# pizero-boardtest.net
KiCad netlist of a schematic drawn in EAGLE
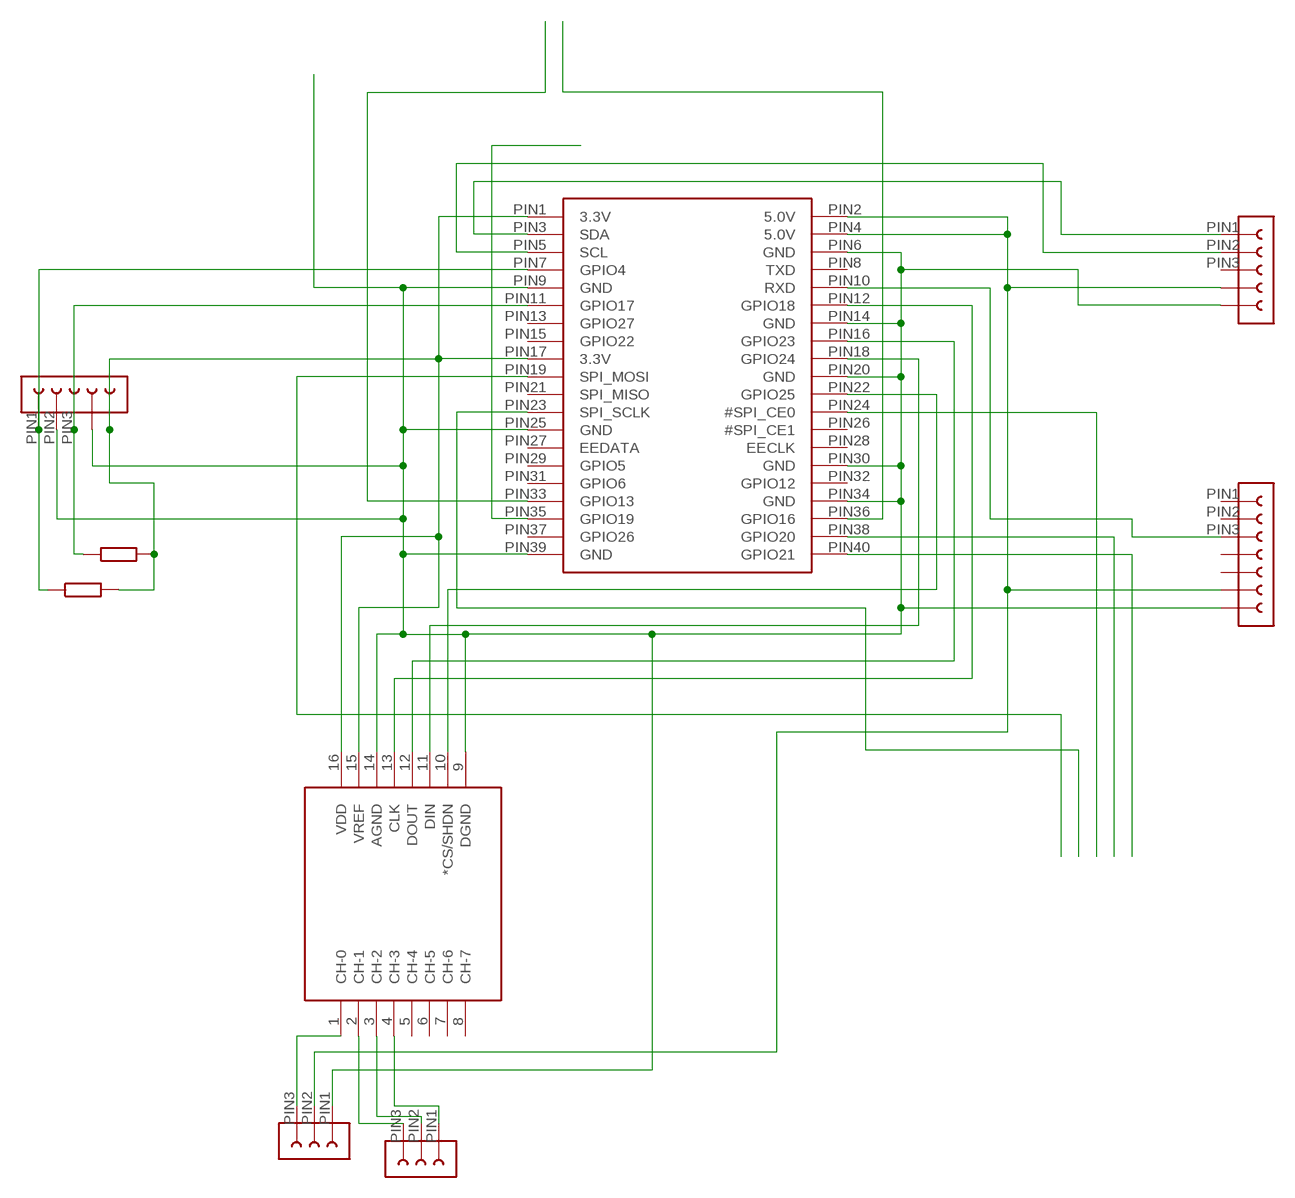
[diagram p0: schematic, sheet 1]

(export (version "E")
  (design (tool "Eeschema 10.0.6"))
  (components
    (comp (ref "ADC")
      (value "ADC-CHIP")
      (footprint "eagle-import:MCP3008-I_SL")
      (libsource (lib "eagle-import") (part "ADC-CHIP"))
    )
    (comp (ref "U$1")
      (value "RPI-CPU")
      (footprint "eagle-import:RPI-CPU")
      (libsource (lib "eagle-import") (part "RPI-CPU"))
    )
    (comp (ref "U$2")
      (value "3PIN-HEADER")
      (footprint "eagle-import:3PIN-HEADER")
      (libsource (lib "eagle-import") (part "3PIN-HEADER"))
    )
    (comp (ref "U$3")
      (value "5PIN-HEADER")
      (footprint "eagle-import:5PIN-HEADER")
      (libsource (lib "eagle-import") (part "5PIN-HEADER"))
    )
    (comp (ref "U$4")
      (value "10KO-RESISTOR")
      (footprint "eagle-import:10KO-RESISTOR")
      (libsource (lib "eagle-import") (part "10KO-RESISTOR"))
    )
    (comp (ref "U$5")
      (value "10KO-RESISTOR")
      (footprint "eagle-import:10KO-RESISTOR")
      (libsource (lib "eagle-import") (part "10KO-RESISTOR"))
    )
    (comp (ref "U$6")
      (value "3PIN-HEADER")
      (footprint "eagle-import:3PIN-HEADER")
      (libsource (lib "eagle-import") (part "3PIN-HEADER"))
    )
    (comp (ref "U$8")
      (value "5PIN-HEADER")
      (footprint "eagle-import:5PIN-HEADER")
      (libsource (lib "eagle-import") (part "5PIN-HEADER"))
    )
    (comp (ref "U$9")
      (value "7PIN-HEADER")
      (footprint "eagle-import:7PIN-HEADER")
      (libsource (lib "eagle-import") (part "7PIN-HEADER"))
    )
  )
  (nets
    (net (code "1") (name "Net-(ADC-*CS{slash}SHDN)") (class "Default")
      (node (ref "ADC") (pin "10") (pinfunction "*CS/SHDN_10") (pintype "bidirectional"))
      (node (ref "U$1") (pin "PIN22") (pinfunction "GPIO25_PIN22") (pintype "bidirectional"))
    )
    (net (code "2") (name "Net-(ADC-AGND)") (class "Default")
      (node (ref "ADC") (pin "14") (pinfunction "AGND_14") (pintype "bidirectional"))
      (node (ref "ADC") (pin "9") (pinfunction "DGND_9") (pintype "bidirectional"))
      (node (ref "U$1") (pin "PIN14") (pinfunction "GND_PIN14") (pintype "bidirectional"))
      (node (ref "U$1") (pin "PIN20") (pinfunction "GND_PIN20") (pintype "bidirectional"))
      (node (ref "U$1") (pin "PIN25") (pinfunction "GND_PIN25") (pintype "bidirectional"))
      (node (ref "U$1") (pin "PIN30") (pinfunction "GND_PIN30") (pintype "bidirectional"))
      (node (ref "U$1") (pin "PIN34") (pinfunction "GND_PIN34") (pintype "bidirectional"))
      (node (ref "U$1") (pin "PIN39") (pinfunction "GND_PIN39") (pintype "bidirectional"))
      (node (ref "U$1") (pin "PIN6") (pinfunction "GND_PIN6") (pintype "bidirectional"))
      (node (ref "U$1") (pin "PIN9") (pinfunction "GND_PIN9") (pintype "bidirectional"))
      (node (ref "U$3") (pin "PIN2") (pinfunction "P$2_PIN2") (pintype "passive"))
      (node (ref "U$3") (pin "PIN4") (pinfunction "P$4_PIN4") (pintype "passive"))
      (node (ref "U$6") (pin "PIN1") (pinfunction "P$1_PIN1") (pintype "passive"))
      (node (ref "U$8") (pin "PIN5") (pinfunction "P$5_PIN5") (pintype "passive"))
      (node (ref "U$9") (pin "PIN7") (pinfunction "P$7_PIN7") (pintype "passive"))
    )
    (net (code "3") (name "Net-(ADC-CH-0)") (class "Default")
      (node (ref "ADC") (pin "1") (pinfunction "CH-0_1") (pintype "bidirectional"))
      (node (ref "U$6") (pin "PIN3") (pinfunction "P$3_PIN3") (pintype "passive"))
    )
    (net (code "4") (name "Net-(ADC-CH-1)") (class "Default")
      (node (ref "ADC") (pin "2") (pinfunction "CH-1_2") (pintype "bidirectional"))
      (node (ref "U$2") (pin "PIN3") (pinfunction "P$3_PIN3") (pintype "passive"))
    )
    (net (code "5") (name "Net-(ADC-CH-2)") (class "Default")
      (node (ref "ADC") (pin "3") (pinfunction "CH-2_3") (pintype "bidirectional"))
      (node (ref "U$2") (pin "PIN2") (pinfunction "P$2_PIN2") (pintype "passive"))
    )
    (net (code "6") (name "Net-(ADC-CH-3)") (class "Default")
      (node (ref "ADC") (pin "4") (pinfunction "CH-3_4") (pintype "bidirectional"))
      (node (ref "U$2") (pin "PIN1") (pinfunction "P$1_PIN1") (pintype "passive"))
    )
    (net (code "7") (name "Net-(ADC-CLK)") (class "Default")
      (node (ref "ADC") (pin "13") (pinfunction "CLK_13") (pintype "bidirectional"))
      (node (ref "U$1") (pin "PIN12") (pinfunction "GPIO18_PIN12") (pintype "bidirectional"))
    )
    (net (code "8") (name "Net-(ADC-DIN)") (class "Default")
      (node (ref "ADC") (pin "11") (pinfunction "DIN_11") (pintype "bidirectional"))
      (node (ref "U$1") (pin "PIN18") (pinfunction "GPIO24_PIN18") (pintype "bidirectional"))
    )
    (net (code "9") (name "Net-(ADC-DOUT)") (class "Default")
      (node (ref "ADC") (pin "12") (pinfunction "DOUT_12") (pintype "bidirectional"))
      (node (ref "U$1") (pin "PIN16") (pinfunction "GPIO23_PIN16") (pintype "bidirectional"))
    )
    (net (code "10") (name "Net-(ADC-VDD)") (class "Default")
      (node (ref "ADC") (pin "15") (pinfunction "VREF_15") (pintype "bidirectional"))
      (node (ref "ADC") (pin "16") (pinfunction "VDD_16") (pintype "bidirectional"))
      (node (ref "U$1") (pin "PIN1") (pinfunction "3.3V_PIN1") (pintype "bidirectional"))
      (node (ref "U$1") (pin "PIN17") (pinfunction "3.3V_PIN17") (pintype "bidirectional"))
      (node (ref "U$3") (pin "PIN5") (pinfunction "P$5_PIN5") (pintype "passive"))
      (node (ref "U$4") (pin "P$2") (pinfunction "P$2_P$2") (pintype "bidirectional"))
      (node (ref "U$5") (pin "P$2") (pinfunction "P$2_P$2") (pintype "bidirectional"))
    )
    (net (code "11") (name "Net-(U$1-GPIO4)") (class "Default")
      (node (ref "U$1") (pin "PIN7") (pinfunction "GPIO4_PIN7") (pintype "bidirectional"))
      (node (ref "U$3") (pin "PIN1") (pinfunction "P$1_PIN1") (pintype "passive"))
      (node (ref "U$5") (pin "P$1") (pinfunction "P$1_P$1") (pintype "bidirectional"))
    )
    (net (code "12") (name "Net-(U$1-GPIO17)") (class "Default")
      (node (ref "U$1") (pin "PIN11") (pinfunction "GPIO17_PIN11") (pintype "bidirectional"))
      (node (ref "U$3") (pin "PIN3") (pinfunction "P$3_PIN3") (pintype "passive"))
      (node (ref "U$4") (pin "P$1") (pinfunction "P$1_P$1") (pintype "bidirectional"))
    )
    (net (code "13") (name "Net-(U$1-RXD)") (class "Default")
      (node (ref "U$1") (pin "PIN10") (pinfunction "RXD_PIN10") (pintype "bidirectional"))
      (node (ref "U$9") (pin "PIN3") (pinfunction "P$3_PIN3") (pintype "passive"))
    )
    (net (code "14") (name "Net-(U$1-SCL)") (class "Default")
      (node (ref "U$1") (pin "PIN5") (pinfunction "SCL_PIN5") (pintype "bidirectional"))
      (node (ref "U$8") (pin "PIN2") (pinfunction "P$2_PIN2") (pintype "passive"))
    )
    (net (code "15") (name "Net-(U$1-SDA)") (class "Default")
      (node (ref "U$1") (pin "PIN3") (pinfunction "SDA_PIN3") (pintype "bidirectional"))
      (node (ref "U$8") (pin "PIN1") (pinfunction "P$1_PIN1") (pintype "passive"))
    )
    (net (code "16") (name "Net-(U$6-P$2)") (class "Default")
      (node (ref "U$1") (pin "PIN2") (pinfunction "5.0V_PIN2") (pintype "bidirectional"))
      (node (ref "U$1") (pin "PIN4") (pinfunction "5.0V_PIN4") (pintype "bidirectional"))
      (node (ref "U$6") (pin "PIN2") (pinfunction "P$2_PIN2") (pintype "passive"))
      (node (ref "U$8") (pin "PIN4") (pinfunction "P$4_PIN4") (pintype "passive"))
      (node (ref "U$9") (pin "PIN6") (pinfunction "P$6_PIN6") (pintype "passive"))
    )
    (net (code "17") (name "unconnected-(ADC-CH-4-Pad5)") (class "Default")
      (node (ref "ADC") (pin "5") (pinfunction "CH-4_5") (pintype "bidirectional"))
    )
    (net (code "18") (name "unconnected-(ADC-CH-5-Pad6)") (class "Default")
      (node (ref "ADC") (pin "6") (pinfunction "CH-5_6") (pintype "bidirectional"))
    )
    (net (code "19") (name "unconnected-(ADC-CH-6-Pad7)") (class "Default")
      (node (ref "ADC") (pin "7") (pinfunction "CH-6_7") (pintype "bidirectional"))
    )
    (net (code "20") (name "unconnected-(ADC-CH-7-Pad8)") (class "Default")
      (node (ref "ADC") (pin "8") (pinfunction "CH-7_8") (pintype "bidirectional"))
    )
    (net (code "21") (name "unconnected-(U$1-#SPI_CE0-PadPIN24)") (class "Default")
      (node (ref "U$1") (pin "PIN24") (pinfunction "#SPI_CE0_PIN24") (pintype "bidirectional"))
    )
    (net (code "22") (name "unconnected-(U$1-#SPI_CE1-PadPIN26)") (class "Default")
      (node (ref "U$1") (pin "PIN26") (pinfunction "#SPI_CE1_PIN26") (pintype "bidirectional"))
    )
    (net (code "23") (name "unconnected-(U$1-EECLK-PadPIN28)") (class "Default")
      (node (ref "U$1") (pin "PIN28") (pinfunction "EECLK_PIN28") (pintype "bidirectional"))
    )
    (net (code "24") (name "unconnected-(U$1-EEDATA-PadPIN27)") (class "Default")
      (node (ref "U$1") (pin "PIN27") (pinfunction "EEDATA_PIN27") (pintype "bidirectional"))
    )
    (net (code "25") (name "unconnected-(U$1-GPIO5-PadPIN29)") (class "Default")
      (node (ref "U$1") (pin "PIN29") (pinfunction "GPIO5_PIN29") (pintype "bidirectional"))
    )
    (net (code "26") (name "unconnected-(U$1-GPIO6-PadPIN31)") (class "Default")
      (node (ref "U$1") (pin "PIN31") (pinfunction "GPIO6_PIN31") (pintype "bidirectional"))
    )
    (net (code "27") (name "unconnected-(U$1-GPIO12-PadPIN32)") (class "Default")
      (node (ref "U$1") (pin "PIN32") (pinfunction "GPIO12_PIN32") (pintype "bidirectional"))
    )
    (net (code "28") (name "unconnected-(U$1-GPIO13-PadPIN33)") (class "Default")
      (node (ref "U$1") (pin "PIN33") (pinfunction "GPIO13_PIN33") (pintype "bidirectional"))
    )
    (net (code "29") (name "unconnected-(U$1-GPIO16-PadPIN36)") (class "Default")
      (node (ref "U$1") (pin "PIN36") (pinfunction "GPIO16_PIN36") (pintype "bidirectional"))
    )
    (net (code "30") (name "unconnected-(U$1-GPIO19-PadPIN35)") (class "Default")
      (node (ref "U$1") (pin "PIN35") (pinfunction "GPIO19_PIN35") (pintype "bidirectional"))
    )
    (net (code "31") (name "unconnected-(U$1-GPIO20-PadPIN38)") (class "Default")
      (node (ref "U$1") (pin "PIN38") (pinfunction "GPIO20_PIN38") (pintype "bidirectional"))
    )
    (net (code "32") (name "unconnected-(U$1-GPIO21-PadPIN40)") (class "Default")
      (node (ref "U$1") (pin "PIN40") (pinfunction "GPIO21_PIN40") (pintype "bidirectional"))
    )
    (net (code "33") (name "unconnected-(U$1-GPIO22-PadPIN15)") (class "Default")
      (node (ref "U$1") (pin "PIN15") (pinfunction "GPIO22_PIN15") (pintype "bidirectional"))
    )
    (net (code "34") (name "unconnected-(U$1-GPIO26-PadPIN37)") (class "Default")
      (node (ref "U$1") (pin "PIN37") (pinfunction "GPIO26_PIN37") (pintype "bidirectional"))
    )
    (net (code "35") (name "unconnected-(U$1-GPIO27-PadPIN13)") (class "Default")
      (node (ref "U$1") (pin "PIN13") (pinfunction "GPIO27_PIN13") (pintype "bidirectional"))
    )
    (net (code "36") (name "unconnected-(U$1-SPI_MISO-PadPIN21)") (class "Default")
      (node (ref "U$1") (pin "PIN21") (pinfunction "SPI_MISO_PIN21") (pintype "bidirectional"))
    )
    (net (code "37") (name "unconnected-(U$1-SPI_MOSI-PadPIN19)") (class "Default")
      (node (ref "U$1") (pin "PIN19") (pinfunction "SPI_MOSI_PIN19") (pintype "bidirectional"))
    )
    (net (code "38") (name "unconnected-(U$1-SPI_SCLK-PadPIN23)") (class "Default")
      (node (ref "U$1") (pin "PIN23") (pinfunction "SPI_SCLK_PIN23") (pintype "bidirectional"))
    )
    (net (code "39") (name "unconnected-(U$1-TXD-PadPIN8)") (class "Default")
      (node (ref "U$1") (pin "PIN8") (pinfunction "TXD_PIN8") (pintype "bidirectional"))
    )
    (net (code "40") (name "unconnected-(U$8-P$3-PadPIN3)") (class "Default")
      (node (ref "U$8") (pin "PIN3") (pinfunction "P$3_PIN3") (pintype "passive"))
    )
    (net (code "41") (name "unconnected-(U$9-P$1-PadPIN1)") (class "Default")
      (node (ref "U$9") (pin "PIN1") (pinfunction "P$1_PIN1") (pintype "passive"))
    )
    (net (code "42") (name "unconnected-(U$9-P$2-PadPIN2)") (class "Default")
      (node (ref "U$9") (pin "PIN2") (pinfunction "P$2_PIN2") (pintype "passive"))
    )
    (net (code "43") (name "unconnected-(U$9-P$4-PadPIN4)") (class "Default")
      (node (ref "U$9") (pin "PIN4") (pinfunction "P$4_PIN4") (pintype "passive"))
    )
    (net (code "44") (name "unconnected-(U$9-P$5-PadPIN5)") (class "Default")
      (node (ref "U$9") (pin "PIN5") (pinfunction "P$5_PIN5") (pintype "passive"))
    )
  )
)
